# Linear_Regulator.net
KiCad netlist of a schematic drawn in EAGLE
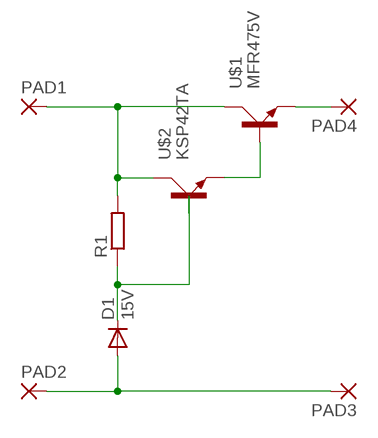
[diagram p0: schematic, sheet 1]

(export (version "E")
  (design (tool "Eeschema 10.0.6"))
  (components
    (comp (ref "D1")
      (value "15V")
      (footprint "eagle-import:SOD80C")
      (libsource (lib "eagle-import") (part "DIODE-SOD80C"))
    )
    (comp (ref "PAD1")
      (value "2,54/0,9")
      (footprint "eagle-import:2,54_0,9")
      (libsource (lib "eagle-import") (part "2,54/0,9"))
    )
    (comp (ref "PAD2")
      (value "2,54/0,9")
      (footprint "eagle-import:2,54_0,9")
      (libsource (lib "eagle-import") (part "2,54/0,9"))
    )
    (comp (ref "PAD3")
      (value "2,54/0,9")
      (footprint "eagle-import:2,54_0,9")
      (libsource (lib "eagle-import") (part "2,54/0,9"))
    )
    (comp (ref "PAD4")
      (value "2,54/0,9")
      (footprint "eagle-import:2,54_0,9")
      (libsource (lib "eagle-import") (part "2,54/0,9"))
    )
    (comp (ref "R1")
      (value "R-EU_R1206")
      (footprint "eagle-import:R1206")
      (libsource (lib "eagle-import") (part "R-EU_R1206"))
    )
    (comp (ref "U$1")
      (value "MFR475V")
      (footprint "eagle-import:TO220AV")
      (libsource (lib "eagle-import") (part "MFR4V75"))
    )
    (comp (ref "U$2")
      (value "KSP42TA")
      (footprint "eagle-import:SOT-92WIDE")
      (libsource (lib "eagle-import") (part "KSP42TA"))
    )
  )
  (nets
    (net (code "1") (name "Net-(D1-PadC)") (class "Default")
      (node (ref "D1") (pin "C") (pinfunction "C_C") (pintype "passive"))
      (node (ref "R1") (pin "1") (pinfunction "1_1") (pintype "passive"))
      (node (ref "U$2") (pin "B") (pinfunction "B_B") (pintype "passive"))
    )
    (net (code "2") (name "Net-(PAD1-P)") (class "Default")
      (node (ref "PAD1") (pin "1") (pinfunction "P_1") (pintype "passive"))
      (node (ref "R1") (pin "2") (pinfunction "2_2") (pintype "passive"))
      (node (ref "U$1") (pin "C") (pinfunction "C_C") (pintype "passive"))
      (node (ref "U$2") (pin "C") (pinfunction "C_C") (pintype "passive"))
    )
    (net (code "3") (name "Net-(PAD2-P)") (class "Default")
      (node (ref "D1") (pin "A") (pinfunction "A_A") (pintype "passive"))
      (node (ref "PAD2") (pin "1") (pinfunction "P_1") (pintype "passive"))
      (node (ref "PAD3") (pin "1") (pinfunction "P_1") (pintype "passive"))
    )
    (net (code "4") (name "Net-(PAD4-P)") (class "Default")
      (node (ref "PAD4") (pin "1") (pinfunction "P_1") (pintype "passive"))
      (node (ref "U$1") (pin "E") (pinfunction "E_E") (pintype "passive"))
    )
    (net (code "5") (name "Net-(U$1-PadB)") (class "Default")
      (node (ref "U$1") (pin "B") (pinfunction "B_B") (pintype "passive"))
      (node (ref "U$2") (pin "E") (pinfunction "E_E") (pintype "passive"))
    )
  )
)
